# PROJECT1.net
KiCad netlist of a schematic drawn in EAGLE
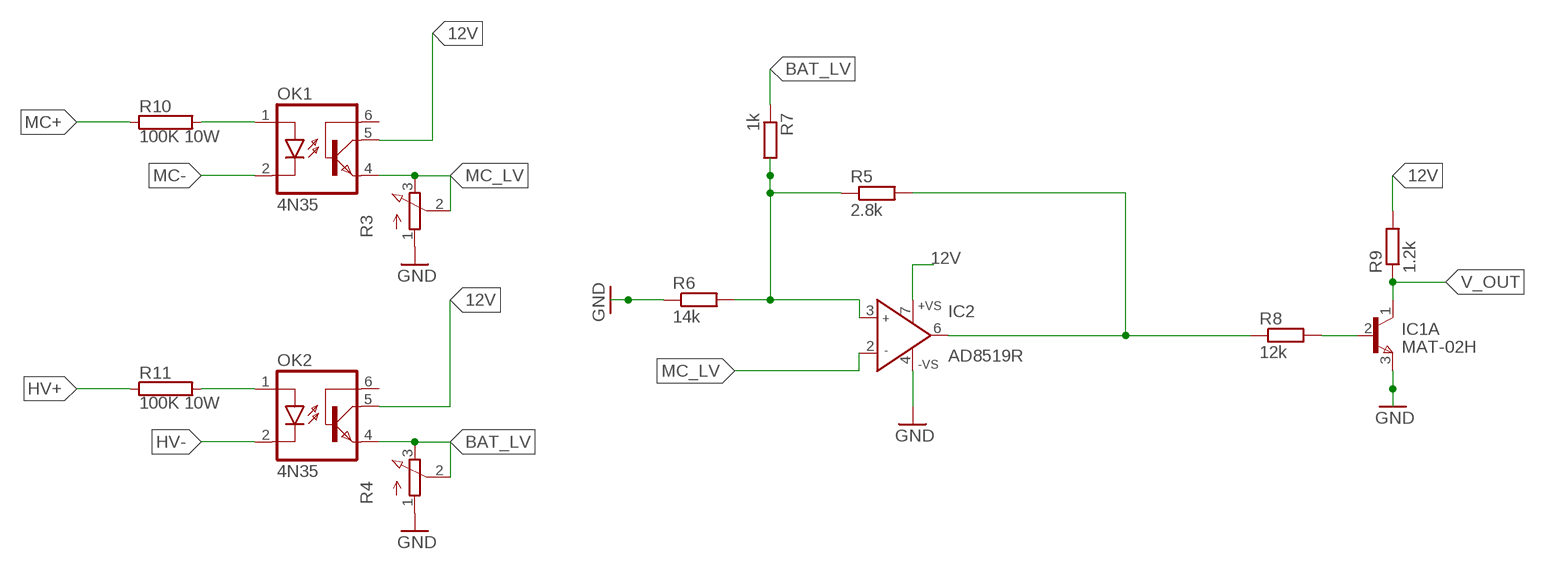
[diagram p0: schematic, sheet 1]

(export (version "E")
  (design (tool "Eeschema 10.0.6"))
  (components
    (comp (ref "IC1")
      (value "MAT-02H")
      (footprint "eagle-import:TO78")
      (libsource (lib "eagle-import") (part "MAT-02H"))
    )
    (comp (ref "IC2")
      (value "AD8519R")
      (footprint "eagle-import:SO8")
      (fields (field (name "MPN") "AD8519ARZ"))
      (libsource (lib "eagle-import") (part "AD8519R"))
    )
    (comp (ref "OK1")
      (value "4N35")
      (footprint "eagle-import:DIL06")
      (fields (field (name "MF") "FAIRCHILD SEMICONDUCTOR"))
      (libsource (lib "eagle-import") (part "4N35"))
    )
    (comp (ref "OK2")
      (value "4N35")
      (footprint "eagle-import:DIL06")
      (fields (field (name "MF") "FAIRCHILD SEMICONDUCTOR"))
      (libsource (lib "eagle-import") (part "4N35"))
    )
    (comp (ref "R3")
      (value "3RP/1610N")
      (footprint "eagle-import:3RP_1610N")
      (libsource (lib "eagle-import") (part "3RP/1610N"))
    )
    (comp (ref "R4")
      (value "3RP/1610N")
      (footprint "eagle-import:3RP_1610N")
      (libsource (lib "eagle-import") (part "3RP/1610N"))
    )
    (comp (ref "R5")
      (value "2.8k")
      (footprint "eagle-import:0207_10")
      (libsource (lib "eagle-import") (part "R-EU_0207/10"))
    )
    (comp (ref "R6")
      (value "14k")
      (footprint "eagle-import:0207_10")
      (libsource (lib "eagle-import") (part "R-EU_0207/10"))
    )
    (comp (ref "R7")
      (value "1k")
      (footprint "eagle-import:0207_10")
      (libsource (lib "eagle-import") (part "R-EU_0207/10"))
    )
    (comp (ref "R8")
      (value "12k")
      (footprint "eagle-import:0207_10")
      (libsource (lib "eagle-import") (part "R-EU_0207/10"))
    )
    (comp (ref "R9")
      (value "1.2k")
      (footprint "eagle-import:0207_10")
      (libsource (lib "eagle-import") (part "R-EU_0207/10"))
    )
    (comp (ref "R10")
      (value "100K 10W")
      (footprint "eagle-import:TO-247-2V")
      (libsource (lib "eagle-import") (part "RMG100-V"))
    )
    (comp (ref "R11")
      (value "100K 10W")
      (footprint "eagle-import:TO-247-2V")
      (libsource (lib "eagle-import") (part "RMG100-V"))
    )
  )
  (nets
    (net (code "1") (name "12V") (class "Default")
      (node (ref "IC2") (pin "7") (pinfunction "+VS_7") (pintype "input"))
      (node (ref "OK1") (pin "5") (pinfunction "COL_5") (pintype "passive"))
      (node (ref "OK2") (pin "5") (pinfunction "COL_5") (pintype "passive"))
      (node (ref "R9") (pin "2") (pinfunction "2_2") (pintype "passive"))
    )
    (net (code "2") (name "BAT_LV") (class "Default")
      (node (ref "OK2") (pin "4") (pinfunction "EMI_4") (pintype "passive"))
      (node (ref "R4") (pin "2") (pinfunction "S_2") (pintype "passive"))
      (node (ref "R4") (pin "3") (pinfunction "E_3") (pintype "passive"))
      (node (ref "R7") (pin "1") (pinfunction "1_1") (pintype "passive"))
    )
    (net (code "3") (name "GND") (class "Default")
      (node (ref "IC1") (pin "3") (pinfunction "E_3") (pintype "passive"))
      (node (ref "IC2") (pin "4") (pinfunction "-VS_4") (pintype "input"))
      (node (ref "R3") (pin "1") (pinfunction "A_1") (pintype "passive"))
      (node (ref "R4") (pin "1") (pinfunction "A_1") (pintype "passive"))
      (node (ref "R6") (pin "1") (pinfunction "1_1") (pintype "passive"))
    )
    (net (code "4") (name "HV+") (class "Default")
      (node (ref "R11") (pin "1") (pinfunction "1_1") (pintype "passive"))
    )
    (net (code "5") (name "HV-") (class "Default")
      (node (ref "OK2") (pin "2") (pinfunction "C_2") (pintype "passive"))
    )
    (net (code "6") (name "MC+") (class "Default")
      (node (ref "R10") (pin "1") (pinfunction "1_1") (pintype "passive"))
    )
    (net (code "7") (name "MC-") (class "Default")
      (node (ref "OK1") (pin "2") (pinfunction "C_2") (pintype "passive"))
    )
    (net (code "8") (name "MC_LV") (class "Default")
      (node (ref "IC2") (pin "2") (pinfunction "IN-_2") (pintype "input"))
      (node (ref "OK1") (pin "4") (pinfunction "EMI_4") (pintype "passive"))
      (node (ref "R3") (pin "2") (pinfunction "S_2") (pintype "passive"))
      (node (ref "R3") (pin "3") (pinfunction "E_3") (pintype "passive"))
    )
    (net (code "9") (name "Net-(IC1A-B)") (class "Default")
      (node (ref "IC1") (pin "2") (pinfunction "B_2") (pintype "passive"))
      (node (ref "R8") (pin "2") (pinfunction "2_2") (pintype "passive"))
    )
    (net (code "10") (name "Net-(IC2-IN+)") (class "Default")
      (node (ref "IC2") (pin "3") (pinfunction "IN+_3") (pintype "input"))
      (node (ref "R5") (pin "1") (pinfunction "1_1") (pintype "passive"))
      (node (ref "R6") (pin "2") (pinfunction "2_2") (pintype "passive"))
      (node (ref "R7") (pin "2") (pinfunction "2_2") (pintype "passive"))
    )
    (net (code "11") (name "Net-(IC2-OUT)") (class "Default")
      (node (ref "IC2") (pin "6") (pinfunction "OUT_6") (pintype "output"))
      (node (ref "R5") (pin "2") (pinfunction "2_2") (pintype "passive"))
      (node (ref "R8") (pin "1") (pinfunction "1_1") (pintype "passive"))
    )
    (net (code "12") (name "Net-(OK1-A)") (class "Default")
      (node (ref "OK1") (pin "1") (pinfunction "A_1") (pintype "passive"))
      (node (ref "R10") (pin "2") (pinfunction "2_2") (pintype "passive"))
    )
    (net (code "13") (name "Net-(OK2-A)") (class "Default")
      (node (ref "OK2") (pin "1") (pinfunction "A_1") (pintype "passive"))
      (node (ref "R11") (pin "2") (pinfunction "2_2") (pintype "passive"))
    )
    (net (code "14") (name "V_OUT") (class "Default")
      (node (ref "IC1") (pin "1") (pinfunction "C_1") (pintype "passive"))
      (node (ref "R9") (pin "1") (pinfunction "1_1") (pintype "passive"))
    )
    (net (code "15") (name "unconnected-(OK1-BAS-Pad6)") (class "Default")
      (node (ref "OK1") (pin "6") (pinfunction "BAS_6") (pintype "passive"))
    )
    (net (code "16") (name "unconnected-(OK2-BAS-Pad6)") (class "Default")
      (node (ref "OK2") (pin "6") (pinfunction "BAS_6") (pintype "passive"))
    )
  )
)
